# Sheet1.net
KiCad netlist of a schematic drawn in Altium Designer
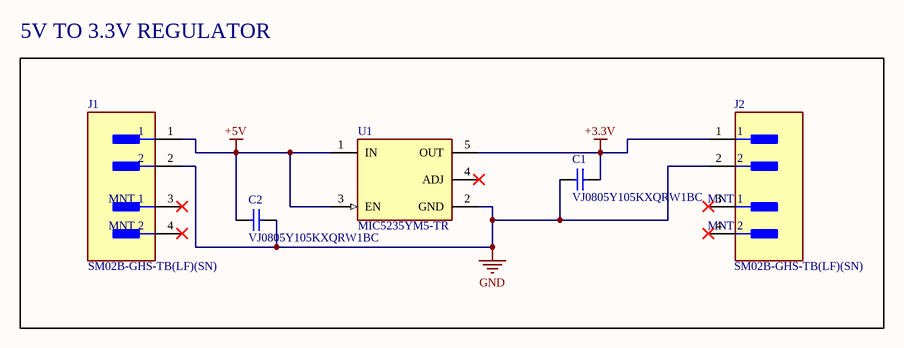
[diagram p0: Sheet1.SchDoc]

(export (version "E")
  (design (tool "Eeschema 10.0.6"))
  (components
    (comp (ref "C1")
      (value "VJ0805Y105KXQRW1BC")
      (footprint "CAPC2013X145X50NL20T20")
      (fields (field (name "MANUFACTURER") "Vitramon"))
      (libsource (lib "Altium Content Vault") (part "CAP"))
    )
    (comp (ref "C2")
      (value "VJ0805Y105KXQRW1BC")
      (footprint "CAPC2013X145X50NL20T20")
      (fields (field (name "MANUFACTURER") "Vitramon"))
      (libsource (lib "Altium Content Vault") (part "CAP"))
    )
    (comp (ref "J1")
      (value "SM02B-GHS-TB(LF)(SN)")
      (footprint "FP-SM02B-GHS-TB_LF_SN-MFG")
      (description "CONN HEADER SMD R/A 2POS 1.25MM")
      (libsource (lib "") (part "56ec3178a87b3978bdc1b3682cd516a_1"))
    )
    (comp (ref "J2")
      (value "SM02B-GHS-TB(LF)(SN)")
      (footprint "FP-SM02B-GHS-TB_LF_SN-MFG")
      (description "CONN HEADER SMD R/A 2POS 1.25MM")
      (libsource (lib "Altium Content Vault") (part "56ec3178a87b3978bdc1b3682cd516a"))
    )
    (comp (ref "U1")
      (value "MIC5235YM5-TR")
      (footprint "FP-SOT23-5LD-PL-1-MFG")
      (description "LDO Regulator Pos 1.24V to 20V 0.15A 5-Pin SOT-23 T/R")
      (fields (field (name "MANUFACTURER") "Microchip Technology"))
      (libsource (lib "Altium Content Vault") (part "8334dd04ef33093fdb03e8dbb784a3e"))
    )
  )
  (nets
    (net (code "1") (name "+3.3V") (class "Default")
      (node (ref "C1") (pin "2") (pinfunction "2_2") (pintype "passive"))
      (node (ref "J2") (pin "1") (pinfunction "1_1") (pintype "passive"))
      (node (ref "U1") (pin "5") (pinfunction "OUT_5") (pintype "power_in"))
    )
    (net (code "2") (name "+5V") (class "Default")
      (node (ref "C2") (pin "1") (pinfunction "1_1") (pintype "passive"))
      (node (ref "J1") (pin "1") (pinfunction "1_1") (pintype "passive"))
      (node (ref "U1") (pin "1") (pinfunction "IN_1") (pintype "power_in"))
      (node (ref "U1") (pin "3") (pinfunction "EN_3") (pintype "input"))
    )
    (net (code "3") (name "GND") (class "Default")
      (node (ref "C1") (pin "1") (pinfunction "1_1") (pintype "passive"))
      (node (ref "C2") (pin "2") (pinfunction "2_2") (pintype "passive"))
      (node (ref "J1") (pin "2") (pinfunction "2_2") (pintype "passive"))
      (node (ref "J2") (pin "2") (pinfunction "2_2") (pintype "passive"))
      (node (ref "U1") (pin "2") (pinfunction "GND_2") (pintype "power_in"))
    )
    (net (code "4") (name "unconnected-(J1-MNT_1-Pad3)") (class "Default")
      (node (ref "J1") (pin "3") (pinfunction "MNT_1_3") (pintype "passive+no_connect"))
    )
    (net (code "5") (name "unconnected-(J1-MNT_2-Pad4)") (class "Default")
      (node (ref "J1") (pin "4") (pinfunction "MNT_2_4") (pintype "passive+no_connect"))
    )
    (net (code "6") (name "unconnected-(J2-MNT_1-Pad3)") (class "Default")
      (node (ref "J2") (pin "3") (pinfunction "MNT_1_3") (pintype "passive+no_connect"))
    )
    (net (code "7") (name "unconnected-(J2-MNT_2-Pad4)") (class "Default")
      (node (ref "J2") (pin "4") (pinfunction "MNT_2_4") (pintype "passive+no_connect"))
    )
    (net (code "8") (name "unconnected-(U1-ADJ-Pad4)") (class "Default")
      (node (ref "U1") (pin "4") (pinfunction "ADJ_4") (pintype "passive+no_connect"))
    )
  )
)
